# W021B.net
KiCad netlist of a schematic drawn in EAGLE
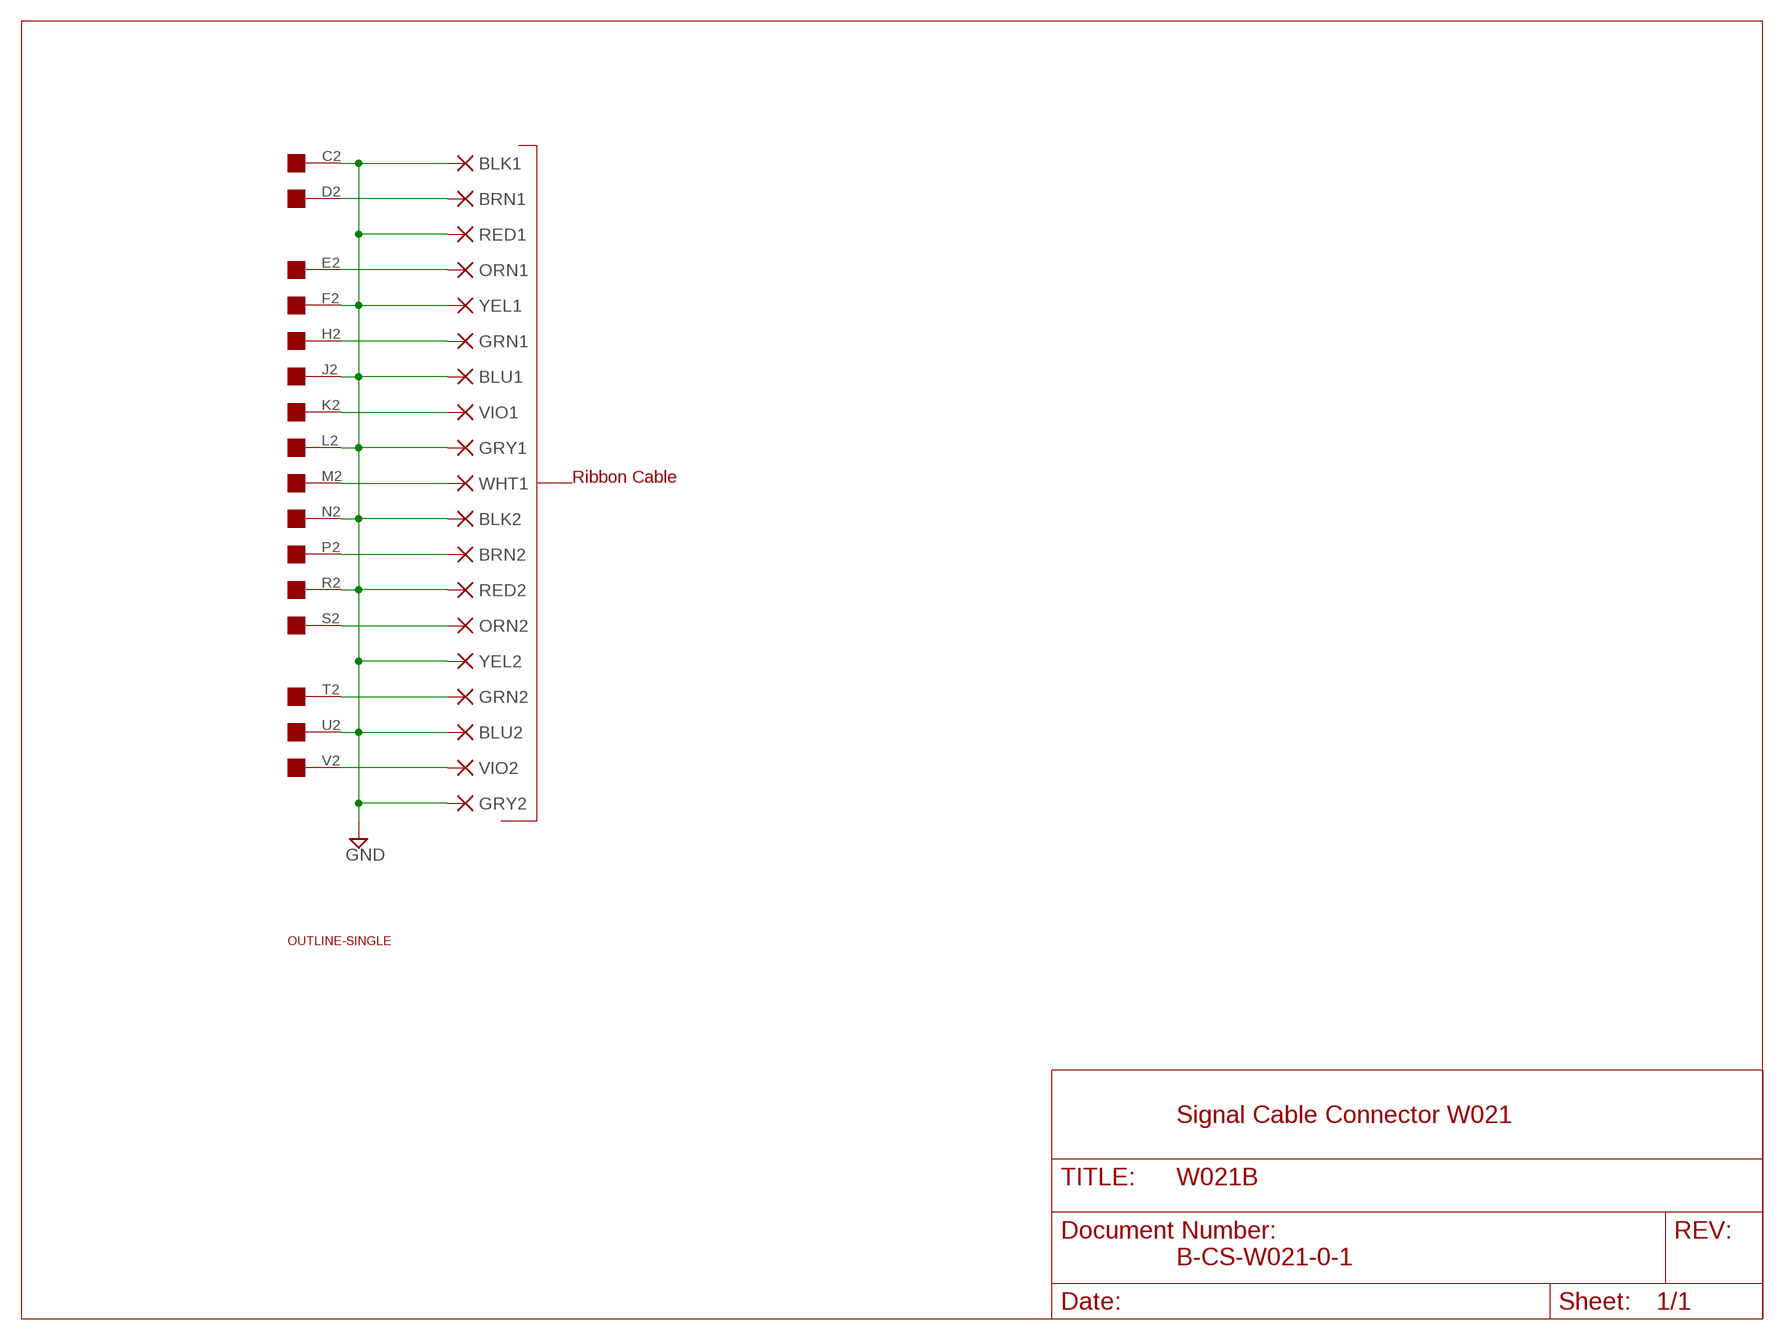
[diagram p0: schematic, sheet 1]

(export (version "E")
  (design (tool "Eeschema 10.0.6"))
  (components
    (comp (ref "BLK1")
      (value "PAD-0465")
      (footprint "eagle-import:0465")
      (libsource (lib "eagle-import") (part "PAD-0465"))
    )
    (comp (ref "BLK2")
      (value "PAD-0465")
      (footprint "eagle-import:0465")
      (libsource (lib "eagle-import") (part "PAD-0465"))
    )
    (comp (ref "BLU1")
      (value "PAD-0465")
      (footprint "eagle-import:0465")
      (libsource (lib "eagle-import") (part "PAD-0465"))
    )
    (comp (ref "BLU2")
      (value "PAD-0465")
      (footprint "eagle-import:0465")
      (libsource (lib "eagle-import") (part "PAD-0465"))
    )
    (comp (ref "BRN1")
      (value "PAD-0465")
      (footprint "eagle-import:0465")
      (libsource (lib "eagle-import") (part "PAD-0465"))
    )
    (comp (ref "BRN2")
      (value "PAD-0465")
      (footprint "eagle-import:0465")
      (libsource (lib "eagle-import") (part "PAD-0465"))
    )
    (comp (ref "GRN1")
      (value "PAD-0465")
      (footprint "eagle-import:0465")
      (libsource (lib "eagle-import") (part "PAD-0465"))
    )
    (comp (ref "GRN2")
      (value "PAD-0465")
      (footprint "eagle-import:0465")
      (libsource (lib "eagle-import") (part "PAD-0465"))
    )
    (comp (ref "GRY1")
      (value "PAD-0465")
      (footprint "eagle-import:0465")
      (libsource (lib "eagle-import") (part "PAD-0465"))
    )
    (comp (ref "GRY2")
      (value "PAD-0465")
      (footprint "eagle-import:0465")
      (libsource (lib "eagle-import") (part "PAD-0465"))
    )
    (comp (ref "ORN1")
      (value "PAD-0465")
      (footprint "eagle-import:0465")
      (libsource (lib "eagle-import") (part "PAD-0465"))
    )
    (comp (ref "ORN2")
      (value "PAD-0465")
      (footprint "eagle-import:0465")
      (libsource (lib "eagle-import") (part "PAD-0465"))
    )
    (comp (ref "RED1")
      (value "PAD-0465")
      (footprint "eagle-import:0465")
      (libsource (lib "eagle-import") (part "PAD-0465"))
    )
    (comp (ref "RED2")
      (value "PAD-0465")
      (footprint "eagle-import:0465")
      (libsource (lib "eagle-import") (part "PAD-0465"))
    )
    (comp (ref "U$1")
      (value "OUTLINE-SINGLE")
      (footprint "eagle-import:SINGLE")
      (libsource (lib "eagle-import") (part "OUTLINE-SINGLE"))
    )
    (comp (ref "U$2")
      (value "EDGE-1")
      (footprint "eagle-import:EDGE-CON1")
      (libsource (lib "eagle-import") (part "EDGE-1"))
    )
    (comp (ref "VIO1")
      (value "PAD-0465")
      (footprint "eagle-import:0465")
      (libsource (lib "eagle-import") (part "PAD-0465"))
    )
    (comp (ref "VIO2")
      (value "PAD-0465")
      (footprint "eagle-import:0465")
      (libsource (lib "eagle-import") (part "PAD-0465"))
    )
    (comp (ref "WHT1")
      (value "PAD-0465")
      (footprint "eagle-import:0465")
      (libsource (lib "eagle-import") (part "PAD-0465"))
    )
    (comp (ref "YEL1")
      (value "PAD-0465")
      (footprint "eagle-import:0465")
      (libsource (lib "eagle-import") (part "PAD-0465"))
    )
    (comp (ref "YEL2")
      (value "PAD-0465")
      (footprint "eagle-import:0465")
      (libsource (lib "eagle-import") (part "PAD-0465"))
    )
  )
  (nets
    (net (code "1") (name "GND") (class "Default")
      (node (ref "BLK1") (pin "P$1") (pinfunction "P_P$1") (pintype "passive"))
      (node (ref "BLK2") (pin "P$1") (pinfunction "P_P$1") (pintype "passive"))
      (node (ref "BLU1") (pin "P$1") (pinfunction "P_P$1") (pintype "passive"))
      (node (ref "BLU2") (pin "P$1") (pinfunction "P_P$1") (pintype "passive"))
      (node (ref "GRY1") (pin "P$1") (pinfunction "P_P$1") (pintype "passive"))
      (node (ref "GRY2") (pin "P$1") (pinfunction "P_P$1") (pintype "passive"))
      (node (ref "RED1") (pin "P$1") (pinfunction "P_P$1") (pintype "passive"))
      (node (ref "RED2") (pin "P$1") (pinfunction "P_P$1") (pintype "passive"))
      (node (ref "U$2") (pin "C2") (pinfunction "1_C2") (pintype "bidirectional"))
      (node (ref "U$2") (pin "F2") (pinfunction "1_F2") (pintype "bidirectional"))
      (node (ref "U$2") (pin "J2") (pinfunction "1_J2") (pintype "bidirectional"))
      (node (ref "U$2") (pin "L2") (pinfunction "1_L2") (pintype "bidirectional"))
      (node (ref "U$2") (pin "N2") (pinfunction "1_N2") (pintype "bidirectional"))
      (node (ref "U$2") (pin "R2") (pinfunction "1_R2") (pintype "bidirectional"))
      (node (ref "U$2") (pin "U2") (pinfunction "1_U2") (pintype "bidirectional"))
      (node (ref "YEL1") (pin "P$1") (pinfunction "P_P$1") (pintype "passive"))
      (node (ref "YEL2") (pin "P$1") (pinfunction "P_P$1") (pintype "passive"))
    )
    (net (code "2") (name "Net-(BRN1-P)") (class "Default")
      (node (ref "BRN1") (pin "P$1") (pinfunction "P_P$1") (pintype "passive"))
      (node (ref "U$2") (pin "D2") (pinfunction "1_D2") (pintype "bidirectional"))
    )
    (net (code "3") (name "Net-(BRN2-P)") (class "Default")
      (node (ref "BRN2") (pin "P$1") (pinfunction "P_P$1") (pintype "passive"))
      (node (ref "U$2") (pin "P2") (pinfunction "1_P2") (pintype "bidirectional"))
    )
    (net (code "4") (name "Net-(GRN1-P)") (class "Default")
      (node (ref "GRN1") (pin "P$1") (pinfunction "P_P$1") (pintype "passive"))
      (node (ref "U$2") (pin "H2") (pinfunction "1_H2") (pintype "bidirectional"))
    )
    (net (code "5") (name "Net-(GRN2-P)") (class "Default")
      (node (ref "GRN2") (pin "P$1") (pinfunction "P_P$1") (pintype "passive"))
      (node (ref "U$2") (pin "T2") (pinfunction "1_T2") (pintype "bidirectional"))
    )
    (net (code "6") (name "Net-(ORN1-P)") (class "Default")
      (node (ref "ORN1") (pin "P$1") (pinfunction "P_P$1") (pintype "passive"))
      (node (ref "U$2") (pin "E2") (pinfunction "1_E2") (pintype "bidirectional"))
    )
    (net (code "7") (name "Net-(ORN2-P)") (class "Default")
      (node (ref "ORN2") (pin "P$1") (pinfunction "P_P$1") (pintype "passive"))
      (node (ref "U$2") (pin "S2") (pinfunction "1_S2") (pintype "bidirectional"))
    )
    (net (code "8") (name "Net-(U$2I-1)") (class "Default")
      (node (ref "U$2") (pin "K2") (pinfunction "1_K2") (pintype "bidirectional"))
      (node (ref "VIO1") (pin "P$1") (pinfunction "P_P$1") (pintype "passive"))
    )
    (net (code "9") (name "Net-(U$2K-1)") (class "Default")
      (node (ref "U$2") (pin "M2") (pinfunction "1_M2") (pintype "bidirectional"))
      (node (ref "WHT1") (pin "P$1") (pinfunction "P_P$1") (pintype "passive"))
    )
    (net (code "10") (name "Net-(U$2R-1)") (class "Default")
      (node (ref "U$2") (pin "V2") (pinfunction "1_V2") (pintype "bidirectional"))
      (node (ref "VIO2") (pin "P$1") (pinfunction "P_P$1") (pintype "passive"))
    )
  )
)
